# power.net
KiCad netlist of a schematic drawn in Altium Designer
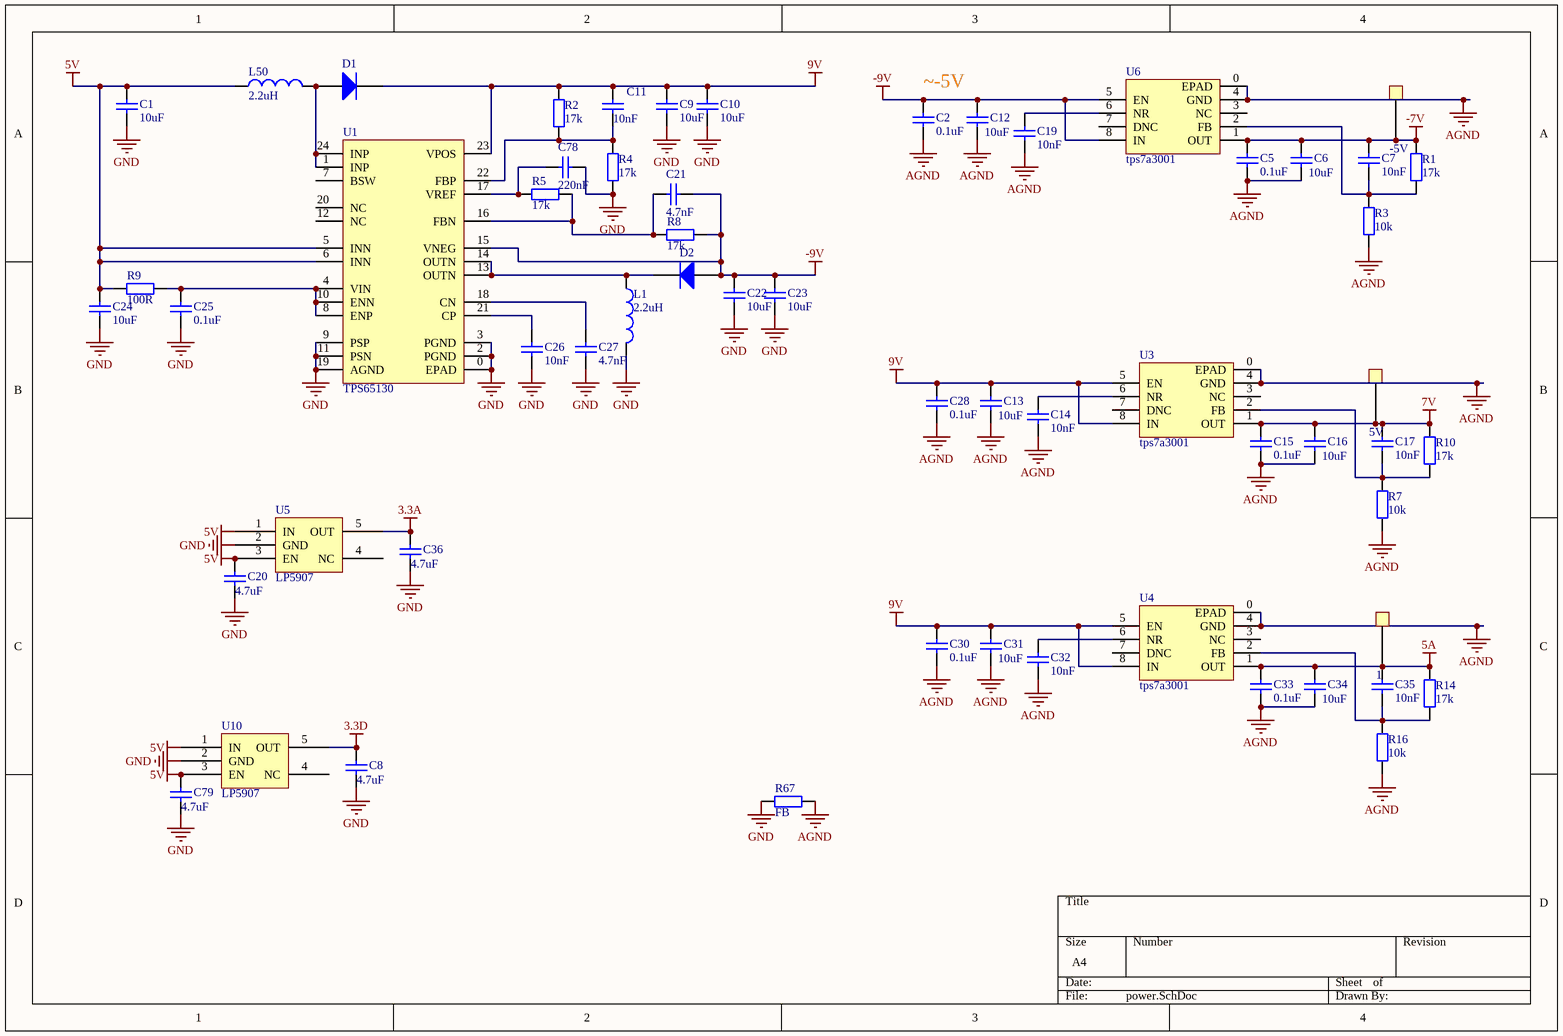
[diagram p0: power.SchDoc]

(export (version "E")
  (design (tool "Eeschema 10.0.6"))
  (components
    (comp (ref "-5V") (value "TestPad") (footprint "TestPad") (libsource (lib "sch") (part "TestPad")))
    (comp (ref "1") (value "TestPad") (footprint "TestPad") (libsource (lib "sch") (part "TestPad")))
    (comp (ref "5V") (value "TestPad") (footprint "TestPad") (libsource (lib "sch") (part "TestPad")))
    (comp (ref "C1")
      (value "10uF")
      (footprint "0603L")
      (description "Capacitor")
      (fields (field (name "PUBLISHER") "Altium Limited"))
      (libsource (lib "RTC6705") (part "Cap"))
    )
    (comp (ref "C2")
      (value "0.1uF")
      (footprint "0603L")
      (description "Capacitor")
      (fields (field (name "PUBLISHER") "Altium Limited"))
      (libsource (lib "RTC6705") (part "Cap"))
    )
    (comp (ref "C5")
      (value "0.1uF")
      (footprint "0603L")
      (description "Capacitor")
      (fields (field (name "PUBLISHER") "Altium Limited"))
      (libsource (lib "RTC6705") (part "Cap"))
    )
    (comp (ref "C6")
      (value "10uF")
      (footprint "0805")
      (description "Capacitor")
      (fields (field (name "PUBLISHER") "Altium Limited"))
      (libsource (lib "RTC6705") (part "Cap"))
    )
    (comp (ref "C7")
      (value "10nF")
      (footprint "0402")
      (description "Capacitor")
      (fields (field (name "PUBLISHER") "Altium Limited"))
      (libsource (lib "RTC6705") (part "Cap"))
    )
    (comp (ref "C8")
      (value "4.7uF")
      (footprint "0603L")
      (description "Capacitor")
      (fields (field (name "PUBLISHER") "Altium Limited"))
      (libsource (lib "RTC6705") (part "Cap"))
    )
    (comp (ref "C9")
      (value "10uF")
      (footprint "0603L")
      (description "Capacitor")
      (fields (field (name "PUBLISHER") "Altium Limited"))
      (libsource (lib "RTC6705") (part "Cap"))
    )
    (comp (ref "C10")
      (value "10uF")
      (footprint "0603L")
      (description "Capacitor")
      (fields (field (name "PUBLISHER") "Altium Limited"))
      (libsource (lib "RTC6705") (part "Cap"))
    )
    (comp (ref "C11")
      (value "10nF")
      (footprint "0402")
      (description "Capacitor")
      (fields (field (name "PUBLISHER") "Altium Limited"))
      (libsource (lib "RTC6705") (part "Cap"))
    )
    (comp (ref "C12")
      (value "10uF")
      (footprint "0805")
      (description "Capacitor")
      (fields (field (name "PUBLISHER") "Altium Limited"))
      (libsource (lib "RTC6705") (part "Cap"))
    )
    (comp (ref "C13")
      (value "10uF")
      (footprint "0805")
      (description "Capacitor")
      (fields (field (name "PUBLISHER") "Altium Limited"))
      (libsource (lib "RTC6705") (part "Cap"))
    )
    (comp (ref "C14")
      (value "10nF")
      (footprint "0402")
      (description "Capacitor")
      (fields (field (name "PUBLISHER") "Altium Limited"))
      (libsource (lib "RTC6705") (part "Cap"))
    )
    (comp (ref "C15")
      (value "0.1uF")
      (footprint "0603L")
      (description "Capacitor")
      (fields (field (name "PUBLISHER") "Altium Limited"))
      (libsource (lib "RTC6705") (part "Cap"))
    )
    (comp (ref "C16")
      (value "10uF")
      (footprint "0805")
      (description "Capacitor")
      (fields (field (name "PUBLISHER") "Altium Limited"))
      (libsource (lib "RTC6705") (part "Cap"))
    )
    (comp (ref "C17")
      (value "10nF")
      (footprint "0402")
      (description "Capacitor")
      (fields (field (name "PUBLISHER") "Altium Limited"))
      (libsource (lib "RTC6705") (part "Cap"))
    )
    (comp (ref "C19")
      (value "10nF")
      (footprint "0402")
      (description "Capacitor")
      (fields (field (name "PUBLISHER") "Altium Limited"))
      (libsource (lib "RTC6705") (part "Cap"))
    )
    (comp (ref "C20")
      (value "4.7uF")
      (footprint "0603L")
      (description "Capacitor")
      (fields (field (name "PUBLISHER") "Altium Limited"))
      (libsource (lib "RTC6705") (part "Cap"))
    )
    (comp (ref "C21")
      (value "4.7nF")
      (footprint "0402")
      (description "Capacitor")
      (fields (field (name "PUBLISHER") "Altium Limited"))
      (libsource (lib "RTC6705") (part "Cap"))
    )
    (comp (ref "C22")
      (value "10uF")
      (footprint "0603L")
      (description "Capacitor")
      (fields (field (name "PUBLISHER") "Altium Limited"))
      (libsource (lib "RTC6705") (part "Cap"))
    )
    (comp (ref "C23")
      (value "10uF")
      (footprint "0603L")
      (description "Capacitor")
      (fields (field (name "PUBLISHER") "Altium Limited"))
      (libsource (lib "RTC6705") (part "Cap"))
    )
    (comp (ref "C24")
      (value "10uF")
      (footprint "0603L")
      (description "Capacitor")
      (fields (field (name "PUBLISHER") "Altium Limited"))
      (libsource (lib "RTC6705") (part "Cap"))
    )
    (comp (ref "C25")
      (value "0.1uF")
      (footprint "0402")
      (description "Capacitor")
      (fields (field (name "PUBLISHER") "Altium Limited"))
      (libsource (lib "RTC6705") (part "Cap"))
    )
    (comp (ref "C26")
      (value "10nF")
      (footprint "0402")
      (description "Capacitor")
      (fields (field (name "PUBLISHER") "Altium Limited"))
      (libsource (lib "RTC6705") (part "Cap"))
    )
    (comp (ref "C27")
      (value "4.7nF")
      (footprint "0402")
      (description "Capacitor")
      (fields (field (name "PUBLISHER") "Altium Limited"))
      (libsource (lib "RTC6705") (part "Cap"))
    )
    (comp (ref "C28")
      (value "0.1uF")
      (footprint "0603L")
      (description "Capacitor")
      (fields (field (name "PUBLISHER") "Altium Limited"))
      (libsource (lib "RTC6705") (part "Cap"))
    )
    (comp (ref "C30")
      (value "0.1uF")
      (footprint "0603L")
      (description "Capacitor")
      (fields (field (name "PUBLISHER") "Altium Limited"))
      (libsource (lib "RTC6705") (part "Cap"))
    )
    (comp (ref "C31")
      (value "10uF")
      (footprint "0805")
      (description "Capacitor")
      (fields (field (name "PUBLISHER") "Altium Limited"))
      (libsource (lib "RTC6705") (part "Cap"))
    )
    (comp (ref "C32")
      (value "10nF")
      (footprint "0402")
      (description "Capacitor")
      (fields (field (name "PUBLISHER") "Altium Limited"))
      (libsource (lib "RTC6705") (part "Cap"))
    )
    (comp (ref "C33")
      (value "0.1uF")
      (footprint "0603L")
      (description "Capacitor")
      (fields (field (name "PUBLISHER") "Altium Limited"))
      (libsource (lib "RTC6705") (part "Cap"))
    )
    (comp (ref "C34")
      (value "10uF")
      (footprint "0805")
      (description "Capacitor")
      (fields (field (name "PUBLISHER") "Altium Limited"))
      (libsource (lib "RTC6705") (part "Cap"))
    )
    (comp (ref "C35")
      (value "10nF")
      (footprint "0402")
      (description "Capacitor")
      (fields (field (name "PUBLISHER") "Altium Limited"))
      (libsource (lib "RTC6705") (part "Cap"))
    )
    (comp (ref "C36")
      (value "4.7uF")
      (footprint "0603L")
      (description "Capacitor")
      (fields (field (name "PUBLISHER") "Altium Limited"))
      (libsource (lib "RTC6705") (part "Cap"))
    )
    (comp (ref "C78")
      (value "220nF")
      (footprint "0402")
      (description "Capacitor")
      (fields (field (name "PUBLISHER") "Altium Limited"))
      (libsource (lib "RTC6705") (part "Cap"))
    )
    (comp (ref "C79")
      (value "4.7uF")
      (footprint "0603L")
      (description "Capacitor")
      (fields (field (name "PUBLISHER") "Altium Limited"))
      (libsource (lib "RTC6705") (part "Cap"))
    )
    (comp (ref "D1")
      (value "~")
      (footprint "LC-SOD-323")
      (description "High Conductance Fast Diode")
      (fields (field (name "PUBLISHER") "Altium Limited"))
      (libsource (lib "Miscellaneous Devices") (part "Diode 1N4148"))
    )
    (comp (ref "D2")
      (value "~")
      (footprint "LC-SOD-323")
      (description "High Conductance Fast Diode")
      (fields (field (name "PUBLISHER") "Altium Limited"))
      (libsource (lib "Miscellaneous Devices") (part "Diode 1N4148"))
    )
    (comp (ref "L1")
      (value "2.2uH")
      (footprint "L4015")
      (description "Inductor")
      (fields (field (name "PUBLISHER") "Altium Limited"))
      (libsource (lib "Miscellaneous Devices") (part "Inductor"))
    )
    (comp (ref "L50")
      (value "2.2uH")
      (footprint "L4015")
      (description "Inductor")
      (fields (field (name "PUBLISHER") "Altium Limited"))
      (libsource (lib "Miscellaneous Devices") (part "Inductor"))
    )
    (comp (ref "R1")
      (value "17k")
      (footprint "0402")
      (description "Resistor")
      (fields (field (name "PUBLISHER") "Altium Limited"))
      (libsource (lib "") (part "Res2_1"))
    )
    (comp (ref "R2")
      (value "17k")
      (footprint "0402")
      (description "Resistor")
      (fields (field (name "PUBLISHER") "Altium Limited"))
      (libsource (lib "") (part "Res2_1"))
    )
    (comp (ref "R3")
      (value "10k")
      (footprint "0402")
      (description "Resistor")
      (fields (field (name "PUBLISHER") "Altium Limited"))
      (libsource (lib "") (part "Res2_1"))
    )
    (comp (ref "R4")
      (value "17k")
      (footprint "0402")
      (description "Resistor")
      (fields (field (name "PUBLISHER") "Altium Limited"))
      (libsource (lib "") (part "Res2_1"))
    )
    (comp (ref "R5")
      (value "17k")
      (footprint "0402")
      (description "Resistor")
      (fields (field (name "PUBLISHER") "Altium Limited"))
      (libsource (lib "RTC6705") (part "Res2"))
    )
    (comp (ref "R7")
      (value "10k")
      (footprint "0402")
      (description "Resistor")
      (fields (field (name "PUBLISHER") "Altium Limited"))
      (libsource (lib "") (part "Res2_1"))
    )
    (comp (ref "R8")
      (value "17k")
      (footprint "0402")
      (description "Resistor")
      (fields (field (name "PUBLISHER") "Altium Limited"))
      (libsource (lib "") (part "Res2_2"))
    )
    (comp (ref "R9")
      (value "100R")
      (footprint "0402")
      (description "Resistor")
      (fields (field (name "PUBLISHER") "Altium Limited"))
      (libsource (lib "RTC6705") (part "Res2"))
    )
    (comp (ref "R10")
      (value "17k")
      (footprint "0402")
      (description "Resistor")
      (fields (field (name "PUBLISHER") "Altium Limited"))
      (libsource (lib "") (part "Res2_1"))
    )
    (comp (ref "R14")
      (value "17k")
      (footprint "0402")
      (description "Resistor")
      (fields (field (name "PUBLISHER") "Altium Limited"))
      (libsource (lib "") (part "Res2_1"))
    )
    (comp (ref "R16")
      (value "10k")
      (footprint "0402")
      (description "Resistor")
      (fields (field (name "PUBLISHER") "Altium Limited"))
      (libsource (lib "") (part "Res2_1"))
    )
    (comp (ref "R67")
      (value "FB")
      (footprint "0603L")
      (description "Resistor")
      (fields (field (name "PUBLISHER") "Altium Limited"))
      (libsource (lib "RTC6705") (part "Res2"))
    )
    (comp (ref "U1") (value "TPS65130") (footprint "TPS65130") (libsource (lib "sch") (part "TPS65130")))
    (comp (ref "U3")
      (value "tps7a3001")
      (footprint "MSOP8/VSSOP8+PAD")
      (libsource (lib "F4SDR") (part "tps7a3001"))
    )
    (comp (ref "U4")
      (value "tps7a3001")
      (footprint "MSOP8/VSSOP8+PAD")
      (libsource (lib "F4SDR") (part "tps7a3001"))
    )
    (comp (ref "U5") (value "LP5907") (footprint "SOT23-5") (libsource (lib "RTC6705") (part "LP5907")))
    (comp (ref "U6")
      (value "tps7a3001")
      (footprint "MSOP8/VSSOP8+PAD")
      (libsource (lib "F4SDR") (part "tps7a3001"))
    )
    (comp (ref "U10") (value "LP5907") (footprint "SOT23-5") (libsource (lib "RTC6705") (part "LP5907")))
  )
  (nets
    (net (code "1") (name "-7V") (class "Default")
      (node (ref "-5V") (pin "1") (pinfunction "3_1") (pintype "passive"))
      (node (ref "C5") (pin "1") (pinfunction "1_1") (pintype "passive"))
      (node (ref "C6") (pin "2") (pinfunction "2_2") (pintype "passive"))
      (node (ref "C7") (pin "1") (pinfunction "1_1") (pintype "passive"))
      (node (ref "R1") (pin "2") (pinfunction "2_2") (pintype "passive"))
      (node (ref "U6") (pin "1") (pinfunction "OUT_1") (pintype "passive"))
    )
    (net (code "2") (name "-9V") (class "Default")
      (node (ref "C12") (pin "2") (pinfunction "2_2") (pintype "passive"))
      (node (ref "C2") (pin "1") (pinfunction "1_1") (pintype "passive"))
      (node (ref "C21") (pin "2") (pinfunction "2_2") (pintype "passive"))
      (node (ref "C22") (pin "1") (pinfunction "1_1") (pintype "passive"))
      (node (ref "C23") (pin "1") (pinfunction "1_1") (pintype "passive"))
      (node (ref "D2") (pin "1") (pinfunction "A_1") (pintype "passive"))
      (node (ref "R8") (pin "2") (pinfunction "2_2") (pintype "passive"))
      (node (ref "U1") (pin "15") (pinfunction "VNEG_15") (pintype "passive"))
      (node (ref "U6") (pin "5") (pinfunction "EN_5") (pintype "passive"))
      (node (ref "U6") (pin "8") (pinfunction "IN_8") (pintype "passive"))
    )
    (net (code "3") (name "3.3A") (class "Default")
      (node (ref "C36") (pin "2") (pinfunction "2_2") (pintype "passive"))
      (node (ref "U5") (pin "5") (pinfunction "OUT_5") (pintype "passive"))
    )
    (net (code "4") (name "3.3D") (class "Default")
      (node (ref "C8") (pin "2") (pinfunction "2_2") (pintype "passive"))
      (node (ref "U10") (pin "5") (pinfunction "OUT_5") (pintype "passive"))
    )
    (net (code "5") (name "5A") (class "Default")
      (node (ref "1") (pin "1") (pinfunction "3_1") (pintype "passive"))
      (node (ref "C33") (pin "1") (pinfunction "1_1") (pintype "passive"))
      (node (ref "C34") (pin "2") (pinfunction "2_2") (pintype "passive"))
      (node (ref "C35") (pin "1") (pinfunction "1_1") (pintype "passive"))
      (node (ref "R14") (pin "2") (pinfunction "2_2") (pintype "passive"))
      (node (ref "U4") (pin "1") (pinfunction "OUT_1") (pintype "passive"))
    )
    (net (code "6") (name "5V") (class "Default")
      (node (ref "C1") (pin "1") (pinfunction "1_1") (pintype "passive"))
      (node (ref "C20") (pin "2") (pinfunction "2_2") (pintype "passive"))
      (node (ref "C24") (pin "1") (pinfunction "1_1") (pintype "passive"))
      (node (ref "C79") (pin "2") (pinfunction "2_2") (pintype "passive"))
      (node (ref "L50") (pin "1") (pinfunction "1_1") (pintype "passive"))
      (node (ref "R9") (pin "2") (pinfunction "2_2") (pintype "passive"))
      (node (ref "U1") (pin "5") (pinfunction "INN_5") (pintype "passive"))
      (node (ref "U1") (pin "6") (pinfunction "INN_6") (pintype "passive"))
      (node (ref "U10") (pin "1") (pinfunction "IN_1") (pintype "passive"))
      (node (ref "U10") (pin "3") (pinfunction "EN_3") (pintype "passive"))
      (node (ref "U5") (pin "1") (pinfunction "IN_1") (pintype "passive"))
      (node (ref "U5") (pin "3") (pinfunction "EN_3") (pintype "passive"))
    )
    (net (code "7") (name "7V") (class "Default")
      (node (ref "5V") (pin "1") (pinfunction "3_1") (pintype "passive"))
      (node (ref "C15") (pin "1") (pinfunction "1_1") (pintype "passive"))
      (node (ref "C16") (pin "2") (pinfunction "2_2") (pintype "passive"))
      (node (ref "C17") (pin "1") (pinfunction "1_1") (pintype "passive"))
      (node (ref "R10") (pin "2") (pinfunction "2_2") (pintype "passive"))
      (node (ref "U3") (pin "1") (pinfunction "OUT_1") (pintype "passive"))
    )
    (net (code "8") (name "9V") (class "Default")
      (node (ref "C10") (pin "1") (pinfunction "1_1") (pintype "passive"))
      (node (ref "C11") (pin "1") (pinfunction "1_1") (pintype "passive"))
      (node (ref "C13") (pin "2") (pinfunction "2_2") (pintype "passive"))
      (node (ref "C28") (pin "1") (pinfunction "1_1") (pintype "passive"))
      (node (ref "C30") (pin "1") (pinfunction "1_1") (pintype "passive"))
      (node (ref "C31") (pin "2") (pinfunction "2_2") (pintype "passive"))
      (node (ref "C9") (pin "1") (pinfunction "1_1") (pintype "passive"))
      (node (ref "D1") (pin "2") (pinfunction "K_2") (pintype "passive"))
      (node (ref "R2") (pin "2") (pinfunction "2_2") (pintype "passive"))
      (node (ref "U1") (pin "23") (pinfunction "VPOS_23") (pintype "passive"))
      (node (ref "U3") (pin "5") (pinfunction "EN_5") (pintype "passive"))
      (node (ref "U3") (pin "8") (pinfunction "IN_8") (pintype "passive"))
      (node (ref "U4") (pin "5") (pinfunction "EN_5") (pintype "passive"))
      (node (ref "U4") (pin "8") (pinfunction "IN_8") (pintype "passive"))
    )
    (net (code "9") (name "AGND") (class "Default")
      (node (ref "C12") (pin "1") (pinfunction "1_1") (pintype "passive"))
      (node (ref "C13") (pin "1") (pinfunction "1_1") (pintype "passive"))
      (node (ref "C14") (pin "2") (pinfunction "2_2") (pintype "passive"))
      (node (ref "C15") (pin "2") (pinfunction "2_2") (pintype "passive"))
      (node (ref "C16") (pin "1") (pinfunction "1_1") (pintype "passive"))
      (node (ref "C19") (pin "2") (pinfunction "2_2") (pintype "passive"))
      (node (ref "C2") (pin "2") (pinfunction "2_2") (pintype "passive"))
      (node (ref "C28") (pin "2") (pinfunction "2_2") (pintype "passive"))
      (node (ref "C30") (pin "2") (pinfunction "2_2") (pintype "passive"))
      (node (ref "C31") (pin "1") (pinfunction "1_1") (pintype "passive"))
      (node (ref "C32") (pin "2") (pinfunction "2_2") (pintype "passive"))
      (node (ref "C33") (pin "2") (pinfunction "2_2") (pintype "passive"))
      (node (ref "C34") (pin "1") (pinfunction "1_1") (pintype "passive"))
      (node (ref "C5") (pin "2") (pinfunction "2_2") (pintype "passive"))
      (node (ref "C6") (pin "1") (pinfunction "1_1") (pintype "passive"))
      (node (ref "R16") (pin "1") (pinfunction "1_1") (pintype "passive"))
      (node (ref "R3") (pin "1") (pinfunction "1_1") (pintype "passive"))
      (node (ref "R67") (pin "1") (pinfunction "1_1") (pintype "passive"))
      (node (ref "R7") (pin "1") (pinfunction "1_1") (pintype "passive"))
      (node (ref "U3") (pin "0") (pinfunction "EPAD_0") (pintype "passive"))
      (node (ref "U3") (pin "4") (pinfunction "GND_4") (pintype "passive"))
      (node (ref "U4") (pin "0") (pinfunction "EPAD_0") (pintype "passive"))
      (node (ref "U4") (pin "4") (pinfunction "GND_4") (pintype "passive"))
      (node (ref "U6") (pin "0") (pinfunction "EPAD_0") (pintype "passive"))
      (node (ref "U6") (pin "4") (pinfunction "GND_4") (pintype "passive"))
    )
    (net (code "10") (name "GND") (class "Default")
      (node (ref "C1") (pin "2") (pinfunction "2_2") (pintype "passive"))
      (node (ref "C10") (pin "2") (pinfunction "2_2") (pintype "passive"))
      (node (ref "C20") (pin "1") (pinfunction "1_1") (pintype "passive"))
      (node (ref "C22") (pin "2") (pinfunction "2_2") (pintype "passive"))
      (node (ref "C23") (pin "2") (pinfunction "2_2") (pintype "passive"))
      (node (ref "C24") (pin "2") (pinfunction "2_2") (pintype "passive"))
      (node (ref "C25") (pin "2") (pinfunction "2_2") (pintype "passive"))
      (node (ref "C26") (pin "2") (pinfunction "2_2") (pintype "passive"))
      (node (ref "C27") (pin "2") (pinfunction "2_2") (pintype "passive"))
      (node (ref "C36") (pin "1") (pinfunction "1_1") (pintype "passive"))
      (node (ref "C78") (pin "2") (pinfunction "2_2") (pintype "passive"))
      (node (ref "C79") (pin "1") (pinfunction "1_1") (pintype "passive"))
      (node (ref "C8") (pin "1") (pinfunction "1_1") (pintype "passive"))
      (node (ref "C9") (pin "2") (pinfunction "2_2") (pintype "passive"))
      (node (ref "L1") (pin "2") (pinfunction "2_2") (pintype "passive"))
      (node (ref "R4") (pin "1") (pinfunction "1_1") (pintype "passive"))
      (node (ref "R67") (pin "2") (pinfunction "2_2") (pintype "passive"))
      (node (ref "U1") (pin "0") (pinfunction "EPAD_0") (pintype "passive"))
      (node (ref "U1") (pin "11") (pinfunction "PSN_11") (pintype "passive"))
      (node (ref "U1") (pin "19") (pinfunction "AGND_19") (pintype "passive"))
      (node (ref "U1") (pin "2") (pinfunction "PGND_2") (pintype "passive"))
      (node (ref "U1") (pin "3") (pinfunction "PGND_3") (pintype "passive"))
      (node (ref "U1") (pin "9") (pinfunction "PSP_9") (pintype "passive"))
      (node (ref "U10") (pin "2") (pinfunction "GND_2") (pintype "passive"))
      (node (ref "U5") (pin "2") (pinfunction "GND_2") (pintype "passive"))
    )
    (net (code "11") (name "Net-(D1-A)") (class "Default")
      (node (ref "D1") (pin "1") (pinfunction "A_1") (pintype "passive"))
      (node (ref "L50") (pin "2") (pinfunction "2_2") (pintype "passive"))
      (node (ref "U1") (pin "1") (pinfunction "INP_1") (pintype "passive"))
      (node (ref "U1") (pin "24") (pinfunction "INP_24") (pintype "passive"))
    )
    (net (code "12") (name "Net-(D2-K)") (class "Default")
      (node (ref "D2") (pin "2") (pinfunction "K_2") (pintype "passive"))
      (node (ref "L1") (pin "1") (pinfunction "1_1") (pintype "passive"))
      (node (ref "U1") (pin "13") (pinfunction "OUTN_13") (pintype "passive"))
      (node (ref "U1") (pin "14") (pinfunction "OUTN_14") (pintype "passive"))
    )
    (net (code "13") (name "Net-(U1-CN)") (class "Default")
      (node (ref "C27") (pin "1") (pinfunction "1_1") (pintype "passive"))
      (node (ref "U1") (pin "18") (pinfunction "CN_18") (pintype "passive"))
    )
    (net (code "14") (name "Net-(U1-CP)") (class "Default")
      (node (ref "C26") (pin "1") (pinfunction "1_1") (pintype "passive"))
      (node (ref "U1") (pin "21") (pinfunction "CP_21") (pintype "passive"))
    )
    (net (code "15") (name "Net-(U1-ENN)") (class "Default")
      (node (ref "C25") (pin "1") (pinfunction "1_1") (pintype "passive"))
      (node (ref "R9") (pin "1") (pinfunction "1_1") (pintype "passive"))
      (node (ref "U1") (pin "10") (pinfunction "ENN_10") (pintype "passive"))
      (node (ref "U1") (pin "4") (pinfunction "VIN_4") (pintype "passive"))
      (node (ref "U1") (pin "8") (pinfunction "ENP_8") (pintype "passive"))
    )
    (net (code "16") (name "Net-(U1-FBN)") (class "Default")
      (node (ref "C21") (pin "1") (pinfunction "1_1") (pintype "passive"))
      (node (ref "R5") (pin "1") (pinfunction "1_1") (pintype "passive"))
      (node (ref "R8") (pin "1") (pinfunction "1_1") (pintype "passive"))
      (node (ref "U1") (pin "16") (pinfunction "FBN_16") (pintype "passive"))
    )
    (net (code "17") (name "Net-(U1-FBP)") (class "Default")
      (node (ref "C11") (pin "2") (pinfunction "2_2") (pintype "passive"))
      (node (ref "R2") (pin "1") (pinfunction "1_1") (pintype "passive"))
      (node (ref "R4") (pin "2") (pinfunction "2_2") (pintype "passive"))
      (node (ref "U1") (pin "22") (pinfunction "FBP_22") (pintype "passive"))
    )
    (net (code "18") (name "Net-(U1-VREF)") (class "Default")
      (node (ref "C78") (pin "1") (pinfunction "1_1") (pintype "passive"))
      (node (ref "R5") (pin "2") (pinfunction "2_2") (pintype "passive"))
      (node (ref "U1") (pin "17") (pinfunction "VREF_17") (pintype "passive"))
    )
    (net (code "19") (name "Net-(U3-FB)") (class "Default")
      (node (ref "C17") (pin "2") (pinfunction "2_2") (pintype "passive"))
      (node (ref "R10") (pin "1") (pinfunction "1_1") (pintype "passive"))
      (node (ref "R7") (pin "2") (pinfunction "2_2") (pintype "passive"))
      (node (ref "U3") (pin "2") (pinfunction "FB_2") (pintype "passive"))
    )
    (net (code "20") (name "Net-(U3-NR)") (class "Default")
      (node (ref "C14") (pin "1") (pinfunction "1_1") (pintype "passive"))
      (node (ref "U3") (pin "6") (pinfunction "NR_6") (pintype "passive"))
    )
    (net (code "21") (name "Net-(U4-FB)") (class "Default")
      (node (ref "C35") (pin "2") (pinfunction "2_2") (pintype "passive"))
      (node (ref "R14") (pin "1") (pinfunction "1_1") (pintype "passive"))
      (node (ref "R16") (pin "2") (pinfunction "2_2") (pintype "passive"))
      (node (ref "U4") (pin "2") (pinfunction "FB_2") (pintype "passive"))
    )
    (net (code "22") (name "Net-(U4-NR)") (class "Default")
      (node (ref "C32") (pin "1") (pinfunction "1_1") (pintype "passive"))
      (node (ref "U4") (pin "6") (pinfunction "NR_6") (pintype "passive"))
    )
    (net (code "23") (name "Net-(U6-FB)") (class "Default")
      (node (ref "C7") (pin "2") (pinfunction "2_2") (pintype "passive"))
      (node (ref "R1") (pin "1") (pinfunction "1_1") (pintype "passive"))
      (node (ref "R3") (pin "2") (pinfunction "2_2") (pintype "passive"))
      (node (ref "U6") (pin "2") (pinfunction "FB_2") (pintype "passive"))
    )
    (net (code "24") (name "Net-(U6-NR)") (class "Default")
      (node (ref "C19") (pin "1") (pinfunction "1_1") (pintype "passive"))
      (node (ref "U6") (pin "6") (pinfunction "NR_6") (pintype "passive"))
    )
    (net (code "25") (name "unconnected-(U1-BSW-Pad7)") (class "Default")
      (node (ref "U1") (pin "7") (pinfunction "BSW_7") (pintype "passive"))
    )
    (net (code "26") (name "unconnected-(U1-NC-Pad12)") (class "Default")
      (node (ref "U1") (pin "12") (pinfunction "NC_12") (pintype "passive"))
    )
    (net (code "27") (name "unconnected-(U1-NC-Pad20)") (class "Default")
      (node (ref "U1") (pin "20") (pinfunction "NC_20") (pintype "passive"))
    )
    (net (code "28") (name "unconnected-(U3-DNC-Pad7)") (class "Default")
      (node (ref "U3") (pin "7") (pinfunction "DNC_7") (pintype "passive"))
    )
    (net (code "29") (name "unconnected-(U3-NC-Pad3)") (class "Default")
      (node (ref "U3") (pin "3") (pinfunction "NC_3") (pintype "passive"))
    )
    (net (code "30") (name "unconnected-(U4-DNC-Pad7)") (class "Default")
      (node (ref "U4") (pin "7") (pinfunction "DNC_7") (pintype "passive"))
    )
    (net (code "31") (name "unconnected-(U4-NC-Pad3)") (class "Default")
      (node (ref "U4") (pin "3") (pinfunction "NC_3") (pintype "passive"))
    )
    (net (code "32") (name "unconnected-(U5-NC-Pad4)") (class "Default")
      (node (ref "U5") (pin "4") (pinfunction "NC_4") (pintype "passive"))
    )
    (net (code "33") (name "unconnected-(U6-DNC-Pad7)") (class "Default")
      (node (ref "U6") (pin "7") (pinfunction "DNC_7") (pintype "passive"))
    )
    (net (code "34") (name "unconnected-(U6-NC-Pad3)") (class "Default")
      (node (ref "U6") (pin "3") (pinfunction "NC_3") (pintype "passive"))
    )
    (net (code "35") (name "unconnected-(U10-NC-Pad4)") (class "Default")
      (node (ref "U10") (pin "4") (pinfunction "NC_4") (pintype "passive"))
    )
  )
)
